# OuterRing.net
KiCad netlist of a schematic drawn in Altium Designer
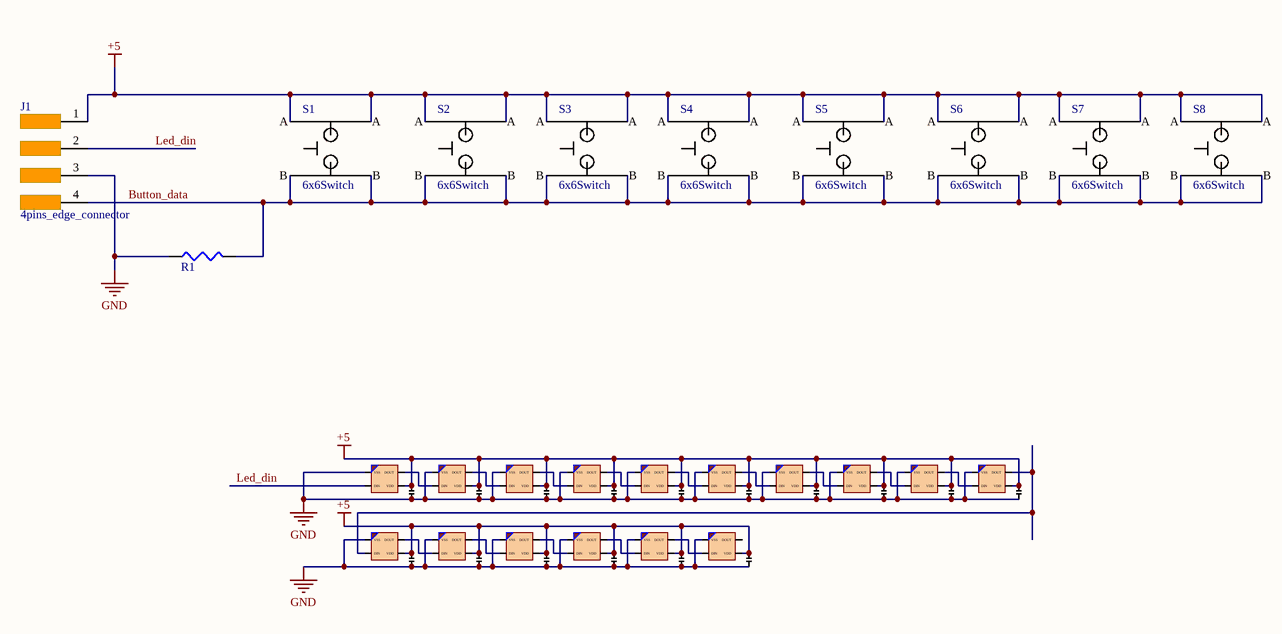
[diagram p0: OuterRing.SchDoc]

(export (version "E")
  (design (tool "Eeschema 10.0.6"))
  (components
    (comp (ref "C1")
      (value "capacitor0.1uf")
      (footprint "Capacitor0805")
      (description "for leds and smol")
      (libsource (lib "WTFschlibra") (part "capacitor0.1uf"))
    )
    (comp (ref "C2")
      (value "capacitor0.1uf")
      (footprint "Capacitor0805")
      (description "for leds and smol")
      (libsource (lib "WTFschlibra") (part "capacitor0.1uf"))
    )
    (comp (ref "C3")
      (value "capacitor0.1uf")
      (footprint "Capacitor0805")
      (description "for leds and smol")
      (libsource (lib "WTFschlibra") (part "capacitor0.1uf"))
    )
    (comp (ref "C4")
      (value "capacitor0.1uf")
      (footprint "Capacitor0805")
      (description "for leds and smol")
      (libsource (lib "WTFschlibra") (part "capacitor0.1uf"))
    )
    (comp (ref "C5")
      (value "capacitor0.1uf")
      (footprint "Capacitor0805")
      (description "for leds and smol")
      (libsource (lib "WTFschlibra") (part "capacitor0.1uf"))
    )
    (comp (ref "C6")
      (value "capacitor0.1uf")
      (footprint "Capacitor0805")
      (description "for leds and smol")
      (libsource (lib "WTFschlibra") (part "capacitor0.1uf"))
    )
    (comp (ref "C7")
      (value "capacitor0.1uf")
      (footprint "Capacitor0805")
      (description "for leds and smol")
      (libsource (lib "WTFschlibra") (part "capacitor0.1uf"))
    )
    (comp (ref "C8")
      (value "capacitor0.1uf")
      (footprint "Capacitor0805")
      (description "for leds and smol")
      (libsource (lib "WTFschlibra") (part "capacitor0.1uf"))
    )
    (comp (ref "C9")
      (value "capacitor0.1uf")
      (footprint "Capacitor0805")
      (description "for leds and smol")
      (libsource (lib "WTFschlibra") (part "capacitor0.1uf"))
    )
    (comp (ref "C10")
      (value "capacitor0.1uf")
      (footprint "Capacitor0805")
      (description "for leds and smol")
      (libsource (lib "WTFschlibra") (part "capacitor0.1uf"))
    )
    (comp (ref "C11")
      (value "capacitor0.1uf")
      (footprint "Capacitor0805")
      (description "for leds and smol")
      (libsource (lib "WTFschlibra") (part "capacitor0.1uf"))
    )
    (comp (ref "C12")
      (value "capacitor0.1uf")
      (footprint "Capacitor0805")
      (description "for leds and smol")
      (libsource (lib "WTFschlibra") (part "capacitor0.1uf"))
    )
    (comp (ref "C13")
      (value "capacitor0.1uf")
      (footprint "Capacitor0805")
      (description "for leds and smol")
      (libsource (lib "WTFschlibra") (part "capacitor0.1uf"))
    )
    (comp (ref "C14")
      (value "capacitor0.1uf")
      (footprint "Capacitor0805")
      (description "for leds and smol")
      (libsource (lib "WTFschlibra") (part "capacitor0.1uf"))
    )
    (comp (ref "C15")
      (value "capacitor0.1uf")
      (footprint "Capacitor0805")
      (description "for leds and smol")
      (libsource (lib "WTFschlibra") (part "capacitor0.1uf"))
    )
    (comp (ref "C16")
      (value "capacitor0.1uf")
      (footprint "Capacitor0805")
      (description "for leds and smol")
      (libsource (lib "WTFschlibra") (part "capacitor0.1uf"))
    )
    (comp (ref "J1")
      (value "4pins_edge_connector")
      (footprint "4pins_edge_connector")
      (libsource (lib "WTFschlibra") (part "4pins_edge_connector"))
    )
    (comp (ref "LED1")
      (value "Ws2812B")
      (footprint "ws2812b")
      (libsource (lib "WTFschlibra") (part "Ws2812B"))
    )
    (comp (ref "LED2")
      (value "Ws2812B")
      (footprint "ws2812b")
      (libsource (lib "WTFschlibra") (part "Ws2812B"))
    )
    (comp (ref "LED3")
      (value "Ws2812B")
      (footprint "ws2812b")
      (libsource (lib "WTFschlibra") (part "Ws2812B"))
    )
    (comp (ref "LED4")
      (value "Ws2812B")
      (footprint "ws2812b")
      (libsource (lib "WTFschlibra") (part "Ws2812B"))
    )
    (comp (ref "LED5")
      (value "Ws2812B")
      (footprint "ws2812b")
      (libsource (lib "WTFschlibra") (part "Ws2812B"))
    )
    (comp (ref "LED6")
      (value "Ws2812B")
      (footprint "ws2812b")
      (libsource (lib "WTFschlibra") (part "Ws2812B"))
    )
    (comp (ref "LED7")
      (value "Ws2812B")
      (footprint "ws2812b")
      (libsource (lib "WTFschlibra") (part "Ws2812B"))
    )
    (comp (ref "LED8")
      (value "Ws2812B")
      (footprint "ws2812b")
      (libsource (lib "WTFschlibra") (part "Ws2812B"))
    )
    (comp (ref "LED9")
      (value "Ws2812B")
      (footprint "ws2812b")
      (libsource (lib "WTFschlibra") (part "Ws2812B"))
    )
    (comp (ref "LED10")
      (value "Ws2812B")
      (footprint "ws2812b")
      (libsource (lib "WTFschlibra") (part "Ws2812B"))
    )
    (comp (ref "LED11")
      (value "Ws2812B")
      (footprint "ws2812b")
      (libsource (lib "WTFschlibra") (part "Ws2812B"))
    )
    (comp (ref "LED12")
      (value "Ws2812B")
      (footprint "ws2812b")
      (libsource (lib "WTFschlibra") (part "Ws2812B"))
    )
    (comp (ref "LED13")
      (value "Ws2812B")
      (footprint "ws2812b")
      (libsource (lib "WTFschlibra") (part "Ws2812B"))
    )
    (comp (ref "LED14")
      (value "Ws2812B")
      (footprint "ws2812b")
      (libsource (lib "WTFschlibra") (part "Ws2812B"))
    )
    (comp (ref "LED15")
      (value "Ws2812B")
      (footprint "ws2812b")
      (libsource (lib "WTFschlibra") (part "Ws2812B"))
    )
    (comp (ref "LED16")
      (value "Ws2812B")
      (footprint "ws2812b")
      (libsource (lib "WTFschlibra") (part "Ws2812B"))
    )
    (comp (ref "R1")
      (value "10K")
      (footprint "R0805")
      (description "Res Thick Film 0805 360 Ohm 1% 0.125W(1/8W) ±100ppm/C Molded SMD Automotive Paper T/R")
      (fields (field (name "TOLERANCE") "1%"))
      (libsource (lib "WTFschlibra") (part "resistor(CRCW0805360RFKEA"))
    )
    (comp (ref "S1")
      (value "6x6Switch")
      (footprint "6x6Switch")
      (libsource (lib "WTFschlibra") (part "6x6Switch"))
    )
    (comp (ref "S2")
      (value "6x6Switch")
      (footprint "6x6Switch")
      (libsource (lib "WTFschlibra") (part "6x6Switch"))
    )
    (comp (ref "S3")
      (value "6x6Switch")
      (footprint "6x6Switch")
      (libsource (lib "WTFschlibra") (part "6x6Switch"))
    )
    (comp (ref "S4")
      (value "6x6Switch")
      (footprint "6x6Switch")
      (libsource (lib "WTFschlibra") (part "6x6Switch"))
    )
    (comp (ref "S5")
      (value "6x6Switch")
      (footprint "6x6Switch")
      (libsource (lib "WTFschlibra") (part "6x6Switch"))
    )
    (comp (ref "S6")
      (value "6x6Switch")
      (footprint "6x6Switch")
      (libsource (lib "WTFschlibra") (part "6x6Switch"))
    )
    (comp (ref "S7")
      (value "6x6Switch")
      (footprint "6x6Switch")
      (libsource (lib "WTFschlibra") (part "6x6Switch"))
    )
    (comp (ref "S8")
      (value "6x6Switch")
      (footprint "6x6Switch")
      (libsource (lib "WTFschlibra") (part "6x6Switch"))
    )
  )
  (nets
    (net (code "1") (name "+5") (class "Default")
      (node (ref "C1") (pin "2") (pinfunction "+_2") (pintype "passive"))
      (node (ref "C10") (pin "2") (pinfunction "+_2") (pintype "passive"))
      (node (ref "C11") (pin "2") (pinfunction "+_2") (pintype "passive"))
      (node (ref "C12") (pin "2") (pinfunction "+_2") (pintype "passive"))
      (node (ref "C13") (pin "2") (pinfunction "+_2") (pintype "passive"))
      (node (ref "C14") (pin "2") (pinfunction "+_2") (pintype "passive"))
      (node (ref "C15") (pin "2") (pinfunction "+_2") (pintype "passive"))
      (node (ref "C16") (pin "2") (pinfunction "+_2") (pintype "passive"))
      (node (ref "C2") (pin "2") (pinfunction "+_2") (pintype "passive"))
      (node (ref "C3") (pin "2") (pinfunction "+_2") (pintype "passive"))
      (node (ref "C4") (pin "2") (pinfunction "+_2") (pintype "passive"))
      (node (ref "C5") (pin "2") (pinfunction "+_2") (pintype "passive"))
      (node (ref "C6") (pin "2") (pinfunction "+_2") (pintype "passive"))
      (node (ref "C7") (pin "2") (pinfunction "+_2") (pintype "passive"))
      (node (ref "C8") (pin "2") (pinfunction "+_2") (pintype "passive"))
      (node (ref "C9") (pin "2") (pinfunction "+_2") (pintype "passive"))
      (node (ref "J1") (pin "1") (pinfunction "+5v_1") (pintype "passive"))
      (node (ref "LED1") (pin "1") (pinfunction "VDD_1") (pintype "passive"))
      (node (ref "LED10") (pin "1") (pinfunction "VDD_1") (pintype "passive"))
      (node (ref "LED11") (pin "1") (pinfunction "VDD_1") (pintype "passive"))
      (node (ref "LED12") (pin "1") (pinfunction "VDD_1") (pintype "passive"))
      (node (ref "LED13") (pin "1") (pinfunction "VDD_1") (pintype "passive"))
      (node (ref "LED14") (pin "1") (pinfunction "VDD_1") (pintype "passive"))
      (node (ref "LED15") (pin "1") (pinfunction "VDD_1") (pintype "passive"))
      (node (ref "LED16") (pin "1") (pinfunction "VDD_1") (pintype "passive"))
      (node (ref "LED2") (pin "1") (pinfunction "VDD_1") (pintype "passive"))
      (node (ref "LED3") (pin "1") (pinfunction "VDD_1") (pintype "passive"))
      (node (ref "LED4") (pin "1") (pinfunction "VDD_1") (pintype "passive"))
      (node (ref "LED5") (pin "1") (pinfunction "VDD_1") (pintype "passive"))
      (node (ref "LED6") (pin "1") (pinfunction "VDD_1") (pintype "passive"))
      (node (ref "LED7") (pin "1") (pinfunction "VDD_1") (pintype "passive"))
      (node (ref "LED8") (pin "1") (pinfunction "VDD_1") (pintype "passive"))
      (node (ref "LED9") (pin "1") (pinfunction "VDD_1") (pintype "passive"))
      (node (ref "S1") (pin "1") (pinfunction "A_1") (pintype "passive"))
      (node (ref "S1") (pin "4") (pinfunction "A_4") (pintype "passive"))
      (node (ref "S2") (pin "1") (pinfunction "A_1") (pintype "passive"))
      (node (ref "S2") (pin "4") (pinfunction "A_4") (pintype "passive"))
      (node (ref "S3") (pin "1") (pinfunction "A_1") (pintype "passive"))
      (node (ref "S3") (pin "4") (pinfunction "A_4") (pintype "passive"))
      (node (ref "S4") (pin "1") (pinfunction "A_1") (pintype "passive"))
      (node (ref "S4") (pin "4") (pinfunction "A_4") (pintype "passive"))
      (node (ref "S5") (pin "1") (pinfunction "A_1") (pintype "passive"))
      (node (ref "S5") (pin "4") (pinfunction "A_4") (pintype "passive"))
      (node (ref "S6") (pin "1") (pinfunction "A_1") (pintype "passive"))
      (node (ref "S6") (pin "4") (pinfunction "A_4") (pintype "passive"))
      (node (ref "S7") (pin "1") (pinfunction "A_1") (pintype "passive"))
      (node (ref "S7") (pin "4") (pinfunction "A_4") (pintype "passive"))
      (node (ref "S8") (pin "1") (pinfunction "A_1") (pintype "passive"))
      (node (ref "S8") (pin "4") (pinfunction "A_4") (pintype "passive"))
    )
    (net (code "2") (name "/Button_data") (class "Default")
      (node (ref "J1") (pin "4") (pinfunction "Button_4") (pintype "passive"))
      (node (ref "R1") (pin "2") (pinfunction "2_2") (pintype "passive"))
      (node (ref "S1") (pin "2") (pinfunction "B_2") (pintype "passive"))
      (node (ref "S1") (pin "3") (pinfunction "B_3") (pintype "passive"))
      (node (ref "S2") (pin "2") (pinfunction "B_2") (pintype "passive"))
      (node (ref "S2") (pin "3") (pinfunction "B_3") (pintype "passive"))
      (node (ref "S3") (pin "2") (pinfunction "B_2") (pintype "passive"))
      (node (ref "S3") (pin "3") (pinfunction "B_3") (pintype "passive"))
      (node (ref "S4") (pin "2") (pinfunction "B_2") (pintype "passive"))
      (node (ref "S4") (pin "3") (pinfunction "B_3") (pintype "passive"))
      (node (ref "S5") (pin "2") (pinfunction "B_2") (pintype "passive"))
      (node (ref "S5") (pin "3") (pinfunction "B_3") (pintype "passive"))
      (node (ref "S6") (pin "2") (pinfunction "B_2") (pintype "passive"))
      (node (ref "S6") (pin "3") (pinfunction "B_3") (pintype "passive"))
      (node (ref "S7") (pin "2") (pinfunction "B_2") (pintype "passive"))
      (node (ref "S7") (pin "3") (pinfunction "B_3") (pintype "passive"))
      (node (ref "S8") (pin "2") (pinfunction "B_2") (pintype "passive"))
      (node (ref "S8") (pin "3") (pinfunction "B_3") (pintype "passive"))
    )
    (net (code "3") (name "/Led_din") (class "Default")
      (node (ref "J1") (pin "2") (pinfunction "Data_2") (pintype "passive"))
      (node (ref "LED1") (pin "4") (pinfunction "DIN_4") (pintype "passive"))
    )
    (net (code "4") (name "GND") (class "Default")
      (node (ref "C1") (pin "1") (pinfunction "-_1") (pintype "passive"))
      (node (ref "C10") (pin "1") (pinfunction "-_1") (pintype "passive"))
      (node (ref "C11") (pin "1") (pinfunction "-_1") (pintype "passive"))
      (node (ref "C12") (pin "1") (pinfunction "-_1") (pintype "passive"))
      (node (ref "C13") (pin "1") (pinfunction "-_1") (pintype "passive"))
      (node (ref "C14") (pin "1") (pinfunction "-_1") (pintype "passive"))
      (node (ref "C15") (pin "1") (pinfunction "-_1") (pintype "passive"))
      (node (ref "C16") (pin "1") (pinfunction "-_1") (pintype "passive"))
      (node (ref "C2") (pin "1") (pinfunction "-_1") (pintype "passive"))
      (node (ref "C3") (pin "1") (pinfunction "-_1") (pintype "passive"))
      (node (ref "C4") (pin "1") (pinfunction "-_1") (pintype "passive"))
      (node (ref "C5") (pin "1") (pinfunction "-_1") (pintype "passive"))
      (node (ref "C6") (pin "1") (pinfunction "-_1") (pintype "passive"))
      (node (ref "C7") (pin "1") (pinfunction "-_1") (pintype "passive"))
      (node (ref "C8") (pin "1") (pinfunction "-_1") (pintype "passive"))
      (node (ref "C9") (pin "1") (pinfunction "-_1") (pintype "passive"))
      (node (ref "J1") (pin "3") (pinfunction "GND_3") (pintype "passive"))
      (node (ref "LED1") (pin "3") (pinfunction "VSS_3") (pintype "passive"))
      (node (ref "LED10") (pin "3") (pinfunction "VSS_3") (pintype "passive"))
      (node (ref "LED11") (pin "3") (pinfunction "VSS_3") (pintype "passive"))
      (node (ref "LED12") (pin "3") (pinfunction "VSS_3") (pintype "passive"))
      (node (ref "LED13") (pin "3") (pinfunction "VSS_3") (pintype "passive"))
      (node (ref "LED14") (pin "3") (pinfunction "VSS_3") (pintype "passive"))
      (node (ref "LED15") (pin "3") (pinfunction "VSS_3") (pintype "passive"))
      (node (ref "LED16") (pin "3") (pinfunction "VSS_3") (pintype "passive"))
      (node (ref "LED2") (pin "3") (pinfunction "VSS_3") (pintype "passive"))
      (node (ref "LED3") (pin "3") (pinfunction "VSS_3") (pintype "passive"))
      (node (ref "LED4") (pin "3") (pinfunction "VSS_3") (pintype "passive"))
      (node (ref "LED5") (pin "3") (pinfunction "VSS_3") (pintype "passive"))
      (node (ref "LED6") (pin "3") (pinfunction "VSS_3") (pintype "passive"))
      (node (ref "LED7") (pin "3") (pinfunction "VSS_3") (pintype "passive"))
      (node (ref "LED8") (pin "3") (pinfunction "VSS_3") (pintype "passive"))
      (node (ref "LED9") (pin "3") (pinfunction "VSS_3") (pintype "passive"))
      (node (ref "R1") (pin "1") (pinfunction "1_1") (pintype "passive"))
    )
    (net (code "5") (name "Net-(LED1-DOUT)") (class "Default")
      (node (ref "LED1") (pin "2") (pinfunction "DOUT_2") (pintype "passive"))
      (node (ref "LED2") (pin "4") (pinfunction "DIN_4") (pintype "passive"))
    )
    (net (code "6") (name "Net-(LED2-DOUT)") (class "Default")
      (node (ref "LED2") (pin "2") (pinfunction "DOUT_2") (pintype "passive"))
      (node (ref "LED3") (pin "4") (pinfunction "DIN_4") (pintype "passive"))
    )
    (net (code "7") (name "Net-(LED3-DOUT)") (class "Default")
      (node (ref "LED3") (pin "2") (pinfunction "DOUT_2") (pintype "passive"))
      (node (ref "LED4") (pin "4") (pinfunction "DIN_4") (pintype "passive"))
    )
    (net (code "8") (name "Net-(LED4-DOUT)") (class "Default")
      (node (ref "LED4") (pin "2") (pinfunction "DOUT_2") (pintype "passive"))
      (node (ref "LED5") (pin "4") (pinfunction "DIN_4") (pintype "passive"))
    )
    (net (code "9") (name "Net-(LED5-DOUT)") (class "Default")
      (node (ref "LED5") (pin "2") (pinfunction "DOUT_2") (pintype "passive"))
      (node (ref "LED6") (pin "4") (pinfunction "DIN_4") (pintype "passive"))
    )
    (net (code "10") (name "Net-(LED6-DOUT)") (class "Default")
      (node (ref "LED6") (pin "2") (pinfunction "DOUT_2") (pintype "passive"))
      (node (ref "LED7") (pin "4") (pinfunction "DIN_4") (pintype "passive"))
    )
    (net (code "11") (name "Net-(LED7-DOUT)") (class "Default")
      (node (ref "LED7") (pin "2") (pinfunction "DOUT_2") (pintype "passive"))
      (node (ref "LED8") (pin "4") (pinfunction "DIN_4") (pintype "passive"))
    )
    (net (code "12") (name "Net-(LED8-DOUT)") (class "Default")
      (node (ref "LED8") (pin "2") (pinfunction "DOUT_2") (pintype "passive"))
      (node (ref "LED9") (pin "4") (pinfunction "DIN_4") (pintype "passive"))
    )
    (net (code "13") (name "Net-(LED10-DIN)") (class "Default")
      (node (ref "LED10") (pin "4") (pinfunction "DIN_4") (pintype "passive"))
      (node (ref "LED9") (pin "2") (pinfunction "DOUT_2") (pintype "passive"))
    )
    (net (code "14") (name "Net-(LED10-DOUT)") (class "Default")
      (node (ref "LED10") (pin "2") (pinfunction "DOUT_2") (pintype "passive"))
      (node (ref "LED11") (pin "4") (pinfunction "DIN_4") (pintype "passive"))
    )
    (net (code "15") (name "Net-(LED11-DOUT)") (class "Default")
      (node (ref "LED11") (pin "2") (pinfunction "DOUT_2") (pintype "passive"))
      (node (ref "LED12") (pin "4") (pinfunction "DIN_4") (pintype "passive"))
    )
    (net (code "16") (name "Net-(LED12-DOUT)") (class "Default")
      (node (ref "LED12") (pin "2") (pinfunction "DOUT_2") (pintype "passive"))
      (node (ref "LED13") (pin "4") (pinfunction "DIN_4") (pintype "passive"))
    )
    (net (code "17") (name "Net-(LED13-DOUT)") (class "Default")
      (node (ref "LED13") (pin "2") (pinfunction "DOUT_2") (pintype "passive"))
      (node (ref "LED14") (pin "4") (pinfunction "DIN_4") (pintype "passive"))
    )
    (net (code "18") (name "Net-(LED14-DOUT)") (class "Default")
      (node (ref "LED14") (pin "2") (pinfunction "DOUT_2") (pintype "passive"))
      (node (ref "LED15") (pin "4") (pinfunction "DIN_4") (pintype "passive"))
    )
    (net (code "19") (name "Net-(LED15-DOUT)") (class "Default")
      (node (ref "LED15") (pin "2") (pinfunction "DOUT_2") (pintype "passive"))
      (node (ref "LED16") (pin "4") (pinfunction "DIN_4") (pintype "passive"))
    )
    (net (code "20") (name "unconnected-(LED16-DOUT-Pad2)") (class "Default")
      (node (ref "LED16") (pin "2") (pinfunction "DOUT_2") (pintype "passive"))
    )
  )
)
